# ELEC-DEM-555Timer.net
KiCad netlist of a schematic drawn in Altium Designer
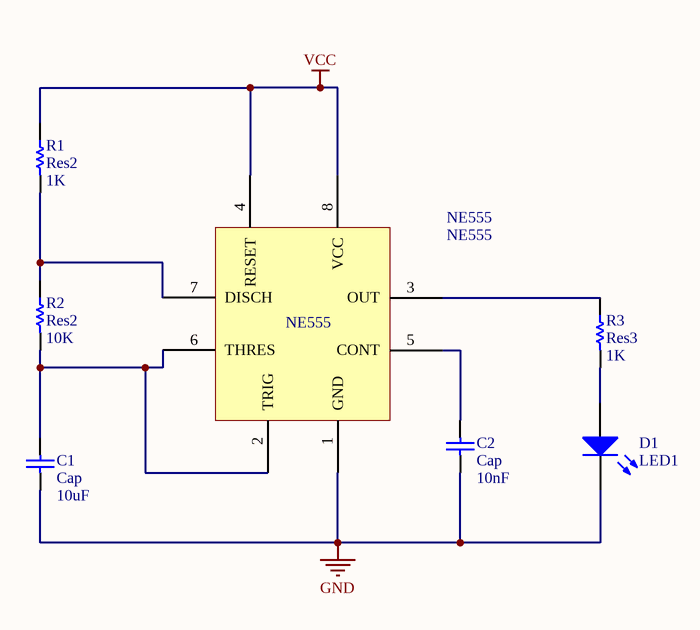
[diagram p0: ELEC-DEM-555Timer.SchDoc]

(export (version "E")
  (design (tool "Eeschema 10.0.6"))
  (components
    (comp (ref "C1")
      (value "Cap")
      (footprint "RAD-0.3")
      (description "Capacitor")
      (fields (field (name "ALTIUM_VALUE") "10uF") (field (name "PUBLISHER") "Altium Limited"))
      (libsource (lib "Miscellaneous Devices") (part "Cap"))
    )
    (comp (ref "C2")
      (value "Cap")
      (footprint "RAD-0.3")
      (description "Capacitor")
      (fields (field (name "ALTIUM_VALUE") "10nF") (field (name "PUBLISHER") "Altium Limited"))
      (libsource (lib "Miscellaneous Devices") (part "Cap"))
    )
    (comp (ref "D1")
      (value "LED1")
      (footprint "LED-1")
      (description "Typical RED GaAs LED")
      (fields (field (name "PUBLISHER") "Altium Limited"))
      (libsource (lib "Miscellaneous Devices") (part "LED1"))
    )
    (comp (ref "NE555") (value "NE555") (libsource (lib "ELEC-DEM-555Timer-Compiled") (part "NE555")))
    (comp (ref "R1")
      (value "Res2")
      (footprint "AXIAL-0.3")
      (description "Resistor")
      (fields (field (name "ALTIUM_VALUE") "1K") (field (name "PUBLISHER") "Altium Limited"))
      (libsource (lib "Miscellaneous Devices") (part "Res1"))
    )
    (comp (ref "R2")
      (value "Res2")
      (footprint "AXIAL-0.3")
      (description "Resistor")
      (fields (field (name "ALTIUM_VALUE") "10K") (field (name "PUBLISHER") "Altium Limited"))
      (libsource (lib "Miscellaneous Devices") (part "Res1"))
    )
    (comp (ref "R3")
      (value "Res3")
      (footprint "AXIAL-0.3")
      (description "Resistor")
      (fields (field (name "ALTIUM_VALUE") "1K") (field (name "PUBLISHER") "Altium Limited"))
      (libsource (lib "Miscellaneous Devices") (part "Res1"))
    )
  )
  (nets
    (net (code "1") (name "GND") (class "Default")
      (node (ref "C1") (pin "2") (pinfunction "2_2") (pintype "passive"))
      (node (ref "C2") (pin "2") (pinfunction "2_2") (pintype "passive"))
      (node (ref "D1") (pin "2") (pinfunction "K_2") (pintype "passive"))
      (node (ref "NE555") (pin "1") (pinfunction "GND_1") (pintype "passive"))
    )
    (net (code "2") (name "Net-(D1-A)") (class "Default")
      (node (ref "D1") (pin "1") (pinfunction "A_1") (pintype "passive"))
      (node (ref "R3") (pin "2") (pinfunction "2_2") (pintype "passive"))
    )
    (net (code "3") (name "Net-(NE555-CONT)") (class "Default")
      (node (ref "C2") (pin "1") (pinfunction "1_1") (pintype "passive"))
      (node (ref "NE555") (pin "5") (pinfunction "CONT_5") (pintype "passive"))
    )
    (net (code "4") (name "Net-(NE555-DISCH)") (class "Default")
      (node (ref "NE555") (pin "7") (pinfunction "DISCH_7") (pintype "passive"))
      (node (ref "R1") (pin "2") (pinfunction "2_2") (pintype "passive"))
      (node (ref "R2") (pin "1") (pinfunction "1_1") (pintype "passive"))
    )
    (net (code "5") (name "Net-(NE555-OUT)") (class "Default")
      (node (ref "NE555") (pin "3") (pinfunction "OUT_3") (pintype "passive"))
      (node (ref "R3") (pin "1") (pinfunction "1_1") (pintype "passive"))
    )
    (net (code "6") (name "Net-(NE555-THRES)") (class "Default")
      (node (ref "C1") (pin "1") (pinfunction "1_1") (pintype "passive"))
      (node (ref "NE555") (pin "2") (pinfunction "TRIG_2") (pintype "passive"))
      (node (ref "NE555") (pin "6") (pinfunction "THRES_6") (pintype "passive"))
      (node (ref "R2") (pin "2") (pinfunction "2_2") (pintype "passive"))
    )
    (net (code "7") (name "VCC") (class "Default")
      (node (ref "NE555") (pin "4") (pinfunction "RESET_4") (pintype "passive"))
      (node (ref "NE555") (pin "8") (pinfunction "VCC_8") (pintype "passive"))
      (node (ref "R1") (pin "1") (pinfunction "1_1") (pintype "passive"))
    )
  )
)
